# AbbotCameraController.net
KiCad netlist of a schematic drawn in EAGLE
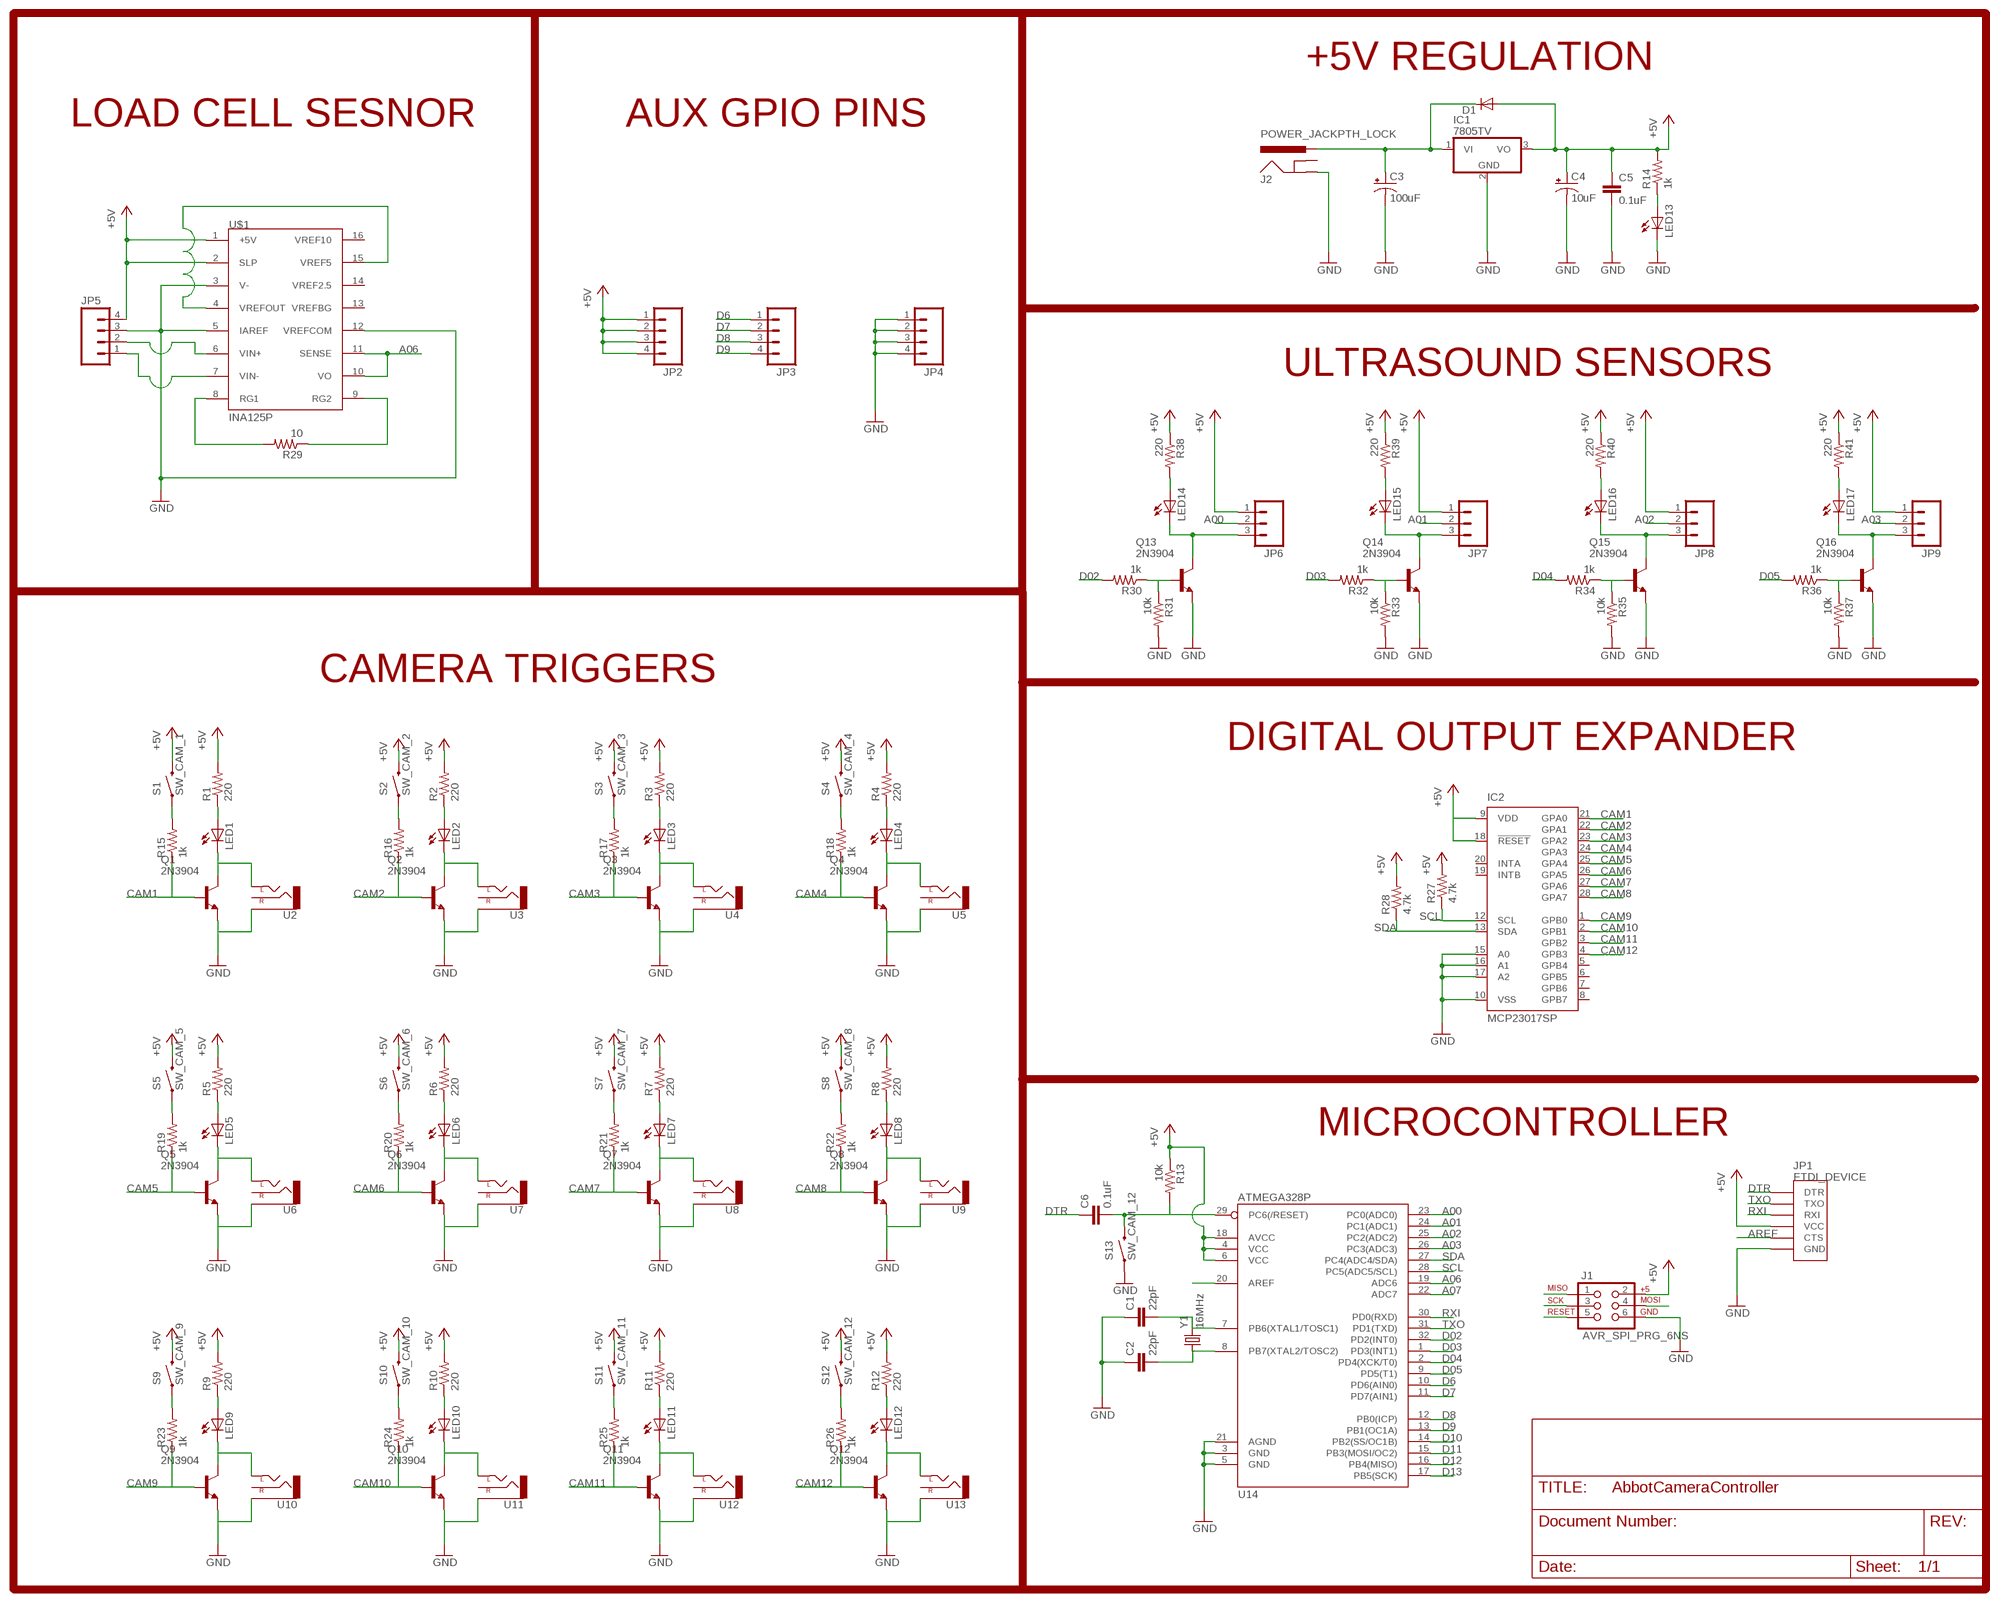
[diagram p0: schematic, sheet 1]

(export (version "E")
  (design (tool "Eeschema 10.0.6"))
  (components
    (comp (ref "C1")
      (value "22pF")
      (footprint "eagle-import:CAP-PTH-SMALL2")
      (libsource (lib "eagle-import") (part "CAPPTH2"))
    )
    (comp (ref "C2")
      (value "22pF")
      (footprint "eagle-import:CAP-PTH-SMALL2")
      (libsource (lib "eagle-import") (part "CAPPTH2"))
    )
    (comp (ref "C3")
      (value "100uF")
      (footprint "eagle-import:E2,5-7")
      (libsource (lib "eagle-import") (part "CPOL-USE2.5-7"))
    )
    (comp (ref "C4")
      (value "10uF")
      (footprint "eagle-import:E2,5-5")
      (libsource (lib "eagle-import") (part "CPOL-USE2.5-5"))
    )
    (comp (ref "C5")
      (value "0.1uF")
      (footprint "eagle-import:C025-025X050")
      (libsource (lib "eagle-import") (part "C-EU025-025X050"))
    )
    (comp (ref "C6")
      (value "0.1uF")
      (footprint "eagle-import:C025-025X050")
      (libsource (lib "eagle-import") (part "C-EU025-025X050"))
    )
    (comp (ref "D1")
      (value "DIODEPTH")
      (footprint "eagle-import:DIODE-1N4001")
      (libsource (lib "eagle-import") (part "DIODEPTH"))
    )
    (comp (ref "IC1")
      (value "7805TV")
      (footprint "eagle-import:TO220V")
      (libsource (lib "eagle-import") (part "78TV05"))
    )
    (comp (ref "IC2")
      (value "MCP23017SP")
      (footprint "eagle-import:DIL28-3")
      (libsource (lib "eagle-import") (part "MCP23017SP"))
    )
    (comp (ref "J1")
      (value "AVR_SPI_PRG_6NS")
      (footprint "eagle-import:2X3-NS")
      (libsource (lib "eagle-import") (part "AVR_SPI_PRG_6NS"))
    )
    (comp (ref "J2")
      (value "POWER_JACKPTH_LOCK")
      (footprint "eagle-import:POWER_JACK_PTH_LOCK")
      (libsource (lib "eagle-import") (part "POWER_JACKPTH_LOCK"))
    )
    (comp (ref "JP1")
      (value "FTDI_DEVICE")
      (footprint "eagle-import:FTDI_DEVICE_SIDE")
      (libsource (lib "eagle-import") (part "FTDI_DEVICE"))
    )
    (comp (ref "JP2")
      (value "M04PTH")
      (footprint "eagle-import:1X04")
      (libsource (lib "eagle-import") (part "M04PTH"))
    )
    (comp (ref "JP3")
      (value "M04PTH")
      (footprint "eagle-import:1X04")
      (libsource (lib "eagle-import") (part "M04PTH"))
    )
    (comp (ref "JP4")
      (value "M04PTH")
      (footprint "eagle-import:1X04")
      (libsource (lib "eagle-import") (part "M04PTH"))
    )
    (comp (ref "JP5")
      (value "M04LONGPADS")
      (footprint "eagle-import:1X04_LONGPADS")
      (libsource (lib "eagle-import") (part "M04LONGPADS"))
    )
    (comp (ref "JP6")
      (value "M03LONGPADS")
      (footprint "eagle-import:1X03_LONGPADS")
      (libsource (lib "eagle-import") (part "M03LONGPADS"))
    )
    (comp (ref "JP7")
      (value "M03LONGPADS")
      (footprint "eagle-import:1X03_LONGPADS")
      (libsource (lib "eagle-import") (part "M03LONGPADS"))
    )
    (comp (ref "JP8")
      (value "M03LONGPADS")
      (footprint "eagle-import:1X03_LONGPADS")
      (libsource (lib "eagle-import") (part "M03LONGPADS"))
    )
    (comp (ref "JP9")
      (value "M03LONGPADS")
      (footprint "eagle-import:1X03_LONGPADS")
      (libsource (lib "eagle-import") (part "M03LONGPADS"))
    )
    (comp (ref "LED1")
      (value "LED5MM")
      (footprint "eagle-import:LED5MM")
      (libsource (lib "eagle-import") (part "LED5MM"))
    )
    (comp (ref "LED2")
      (value "LED5MM")
      (footprint "eagle-import:LED5MM")
      (libsource (lib "eagle-import") (part "LED5MM"))
    )
    (comp (ref "LED3")
      (value "LED5MM")
      (footprint "eagle-import:LED5MM")
      (libsource (lib "eagle-import") (part "LED5MM"))
    )
    (comp (ref "LED4")
      (value "LED5MM")
      (footprint "eagle-import:LED5MM")
      (libsource (lib "eagle-import") (part "LED5MM"))
    )
    (comp (ref "LED5")
      (value "LED5MM")
      (footprint "eagle-import:LED5MM")
      (libsource (lib "eagle-import") (part "LED5MM"))
    )
    (comp (ref "LED6")
      (value "LED5MM")
      (footprint "eagle-import:LED5MM")
      (libsource (lib "eagle-import") (part "LED5MM"))
    )
    (comp (ref "LED7")
      (value "LED5MM")
      (footprint "eagle-import:LED5MM")
      (libsource (lib "eagle-import") (part "LED5MM"))
    )
    (comp (ref "LED8")
      (value "LED5MM")
      (footprint "eagle-import:LED5MM")
      (libsource (lib "eagle-import") (part "LED5MM"))
    )
    (comp (ref "LED9")
      (value "LED5MM")
      (footprint "eagle-import:LED5MM")
      (libsource (lib "eagle-import") (part "LED5MM"))
    )
    (comp (ref "LED10")
      (value "LED5MM")
      (footprint "eagle-import:LED5MM")
      (libsource (lib "eagle-import") (part "LED5MM"))
    )
    (comp (ref "LED11")
      (value "LED5MM")
      (footprint "eagle-import:LED5MM")
      (libsource (lib "eagle-import") (part "LED5MM"))
    )
    (comp (ref "LED12")
      (value "LED5MM")
      (footprint "eagle-import:LED5MM")
      (libsource (lib "eagle-import") (part "LED5MM"))
    )
    (comp (ref "LED13")
      (value "LED5MM")
      (footprint "eagle-import:LED5MM")
      (libsource (lib "eagle-import") (part "LED5MM"))
    )
    (comp (ref "LED14")
      (value "LED5MM")
      (footprint "eagle-import:LED5MM")
      (libsource (lib "eagle-import") (part "LED5MM"))
    )
    (comp (ref "LED15")
      (value "LED5MM")
      (footprint "eagle-import:LED5MM")
      (libsource (lib "eagle-import") (part "LED5MM"))
    )
    (comp (ref "LED16")
      (value "LED5MM")
      (footprint "eagle-import:LED5MM")
      (libsource (lib "eagle-import") (part "LED5MM"))
    )
    (comp (ref "LED17")
      (value "LED5MM")
      (footprint "eagle-import:LED5MM")
      (libsource (lib "eagle-import") (part "LED5MM"))
    )
    (comp (ref "Q1")
      (value "2N3904")
      (footprint "eagle-import:TO92")
      (libsource (lib "eagle-import") (part "2N3904"))
    )
    (comp (ref "Q2")
      (value "2N3904")
      (footprint "eagle-import:TO92")
      (libsource (lib "eagle-import") (part "2N3904"))
    )
    (comp (ref "Q3")
      (value "2N3904")
      (footprint "eagle-import:TO92")
      (libsource (lib "eagle-import") (part "2N3904"))
    )
    (comp (ref "Q4")
      (value "2N3904")
      (footprint "eagle-import:TO92")
      (libsource (lib "eagle-import") (part "2N3904"))
    )
    (comp (ref "Q5")
      (value "2N3904")
      (footprint "eagle-import:TO92")
      (libsource (lib "eagle-import") (part "2N3904"))
    )
    (comp (ref "Q6")
      (value "2N3904")
      (footprint "eagle-import:TO92")
      (libsource (lib "eagle-import") (part "2N3904"))
    )
    (comp (ref "Q7")
      (value "2N3904")
      (footprint "eagle-import:TO92")
      (libsource (lib "eagle-import") (part "2N3904"))
    )
    (comp (ref "Q8")
      (value "2N3904")
      (footprint "eagle-import:TO92")
      (libsource (lib "eagle-import") (part "2N3904"))
    )
    (comp (ref "Q9")
      (value "2N3904")
      (footprint "eagle-import:TO92")
      (libsource (lib "eagle-import") (part "2N3904"))
    )
    (comp (ref "Q10")
      (value "2N3904")
      (footprint "eagle-import:TO92")
      (libsource (lib "eagle-import") (part "2N3904"))
    )
    (comp (ref "Q11")
      (value "2N3904")
      (footprint "eagle-import:TO92")
      (libsource (lib "eagle-import") (part "2N3904"))
    )
    (comp (ref "Q12")
      (value "2N3904")
      (footprint "eagle-import:TO92")
      (libsource (lib "eagle-import") (part "2N3904"))
    )
    (comp (ref "Q13")
      (value "2N3904")
      (footprint "eagle-import:TO92")
      (libsource (lib "eagle-import") (part "2N3904"))
    )
    (comp (ref "Q14")
      (value "2N3904")
      (footprint "eagle-import:TO92")
      (libsource (lib "eagle-import") (part "2N3904"))
    )
    (comp (ref "Q15")
      (value "2N3904")
      (footprint "eagle-import:TO92")
      (libsource (lib "eagle-import") (part "2N3904"))
    )
    (comp (ref "Q16")
      (value "2N3904")
      (footprint "eagle-import:TO92")
      (libsource (lib "eagle-import") (part "2N3904"))
    )
    (comp (ref "R1")
      (value "220")
      (footprint "eagle-import:0207_10")
      (libsource (lib "eagle-import") (part "R-US_0207/10"))
    )
    (comp (ref "R2")
      (value "220")
      (footprint "eagle-import:0207_10")
      (libsource (lib "eagle-import") (part "R-US_0207/10"))
    )
    (comp (ref "R3")
      (value "220")
      (footprint "eagle-import:0207_10")
      (libsource (lib "eagle-import") (part "R-US_0207/10"))
    )
    (comp (ref "R4")
      (value "220")
      (footprint "eagle-import:0207_10")
      (libsource (lib "eagle-import") (part "R-US_0207/10"))
    )
    (comp (ref "R5")
      (value "220")
      (footprint "eagle-import:0207_10")
      (libsource (lib "eagle-import") (part "R-US_0207/10"))
    )
    (comp (ref "R6")
      (value "220")
      (footprint "eagle-import:0207_10")
      (libsource (lib "eagle-import") (part "R-US_0207/10"))
    )
    (comp (ref "R7")
      (value "220")
      (footprint "eagle-import:0207_10")
      (libsource (lib "eagle-import") (part "R-US_0207/10"))
    )
    (comp (ref "R8")
      (value "220")
      (footprint "eagle-import:0207_10")
      (libsource (lib "eagle-import") (part "R-US_0207/10"))
    )
    (comp (ref "R9")
      (value "220")
      (footprint "eagle-import:0207_10")
      (libsource (lib "eagle-import") (part "R-US_0207/10"))
    )
    (comp (ref "R10")
      (value "220")
      (footprint "eagle-import:0207_10")
      (libsource (lib "eagle-import") (part "R-US_0207/10"))
    )
    (comp (ref "R11")
      (value "220")
      (footprint "eagle-import:0207_10")
      (libsource (lib "eagle-import") (part "R-US_0207/10"))
    )
    (comp (ref "R12")
      (value "220")
      (footprint "eagle-import:0207_10")
      (libsource (lib "eagle-import") (part "R-US_0207/10"))
    )
    (comp (ref "R13")
      (value "10k")
      (footprint "eagle-import:0207_10")
      (libsource (lib "eagle-import") (part "R-US_0207/10"))
    )
    (comp (ref "R14")
      (value "1k")
      (footprint "eagle-import:0207_10")
      (libsource (lib "eagle-import") (part "R-US_0207/10"))
    )
    (comp (ref "R15")
      (value "1k")
      (footprint "eagle-import:0207_10")
      (libsource (lib "eagle-import") (part "R-US_0207/10"))
    )
    (comp (ref "R16")
      (value "1k")
      (footprint "eagle-import:0207_10")
      (libsource (lib "eagle-import") (part "R-US_0207/10"))
    )
    (comp (ref "R17")
      (value "1k")
      (footprint "eagle-import:0207_10")
      (libsource (lib "eagle-import") (part "R-US_0207/10"))
    )
    (comp (ref "R18")
      (value "1k")
      (footprint "eagle-import:0207_10")
      (libsource (lib "eagle-import") (part "R-US_0207/10"))
    )
    (comp (ref "R19")
      (value "1k")
      (footprint "eagle-import:0207_10")
      (libsource (lib "eagle-import") (part "R-US_0207/10"))
    )
    (comp (ref "R20")
      (value "1k")
      (footprint "eagle-import:0207_10")
      (libsource (lib "eagle-import") (part "R-US_0207/10"))
    )
    (comp (ref "R21")
      (value "1k")
      (footprint "eagle-import:0207_10")
      (libsource (lib "eagle-import") (part "R-US_0207/10"))
    )
    (comp (ref "R22")
      (value "1k")
      (footprint "eagle-import:0207_10")
      (libsource (lib "eagle-import") (part "R-US_0207/10"))
    )
    (comp (ref "R23")
      (value "1k")
      (footprint "eagle-import:0207_10")
      (libsource (lib "eagle-import") (part "R-US_0207/10"))
    )
    (comp (ref "R24")
      (value "1k")
      (footprint "eagle-import:0207_10")
      (libsource (lib "eagle-import") (part "R-US_0207/10"))
    )
    (comp (ref "R25")
      (value "1k")
      (footprint "eagle-import:0207_10")
      (libsource (lib "eagle-import") (part "R-US_0207/10"))
    )
    (comp (ref "R26")
      (value "1k")
      (footprint "eagle-import:0207_10")
      (libsource (lib "eagle-import") (part "R-US_0207/10"))
    )
    (comp (ref "R27")
      (value "4.7k")
      (footprint "eagle-import:0207_10")
      (libsource (lib "eagle-import") (part "R-US_0207/10"))
    )
    (comp (ref "R28")
      (value "4.7k")
      (footprint "eagle-import:0207_10")
      (libsource (lib "eagle-import") (part "R-US_0207/10"))
    )
    (comp (ref "R29")
      (value "10")
      (footprint "eagle-import:0207_10")
      (libsource (lib "eagle-import") (part "R-US_0207/10"))
    )
    (comp (ref "R30")
      (value "1k")
      (footprint "eagle-import:0207_10")
      (libsource (lib "eagle-import") (part "R-US_0207/10"))
    )
    (comp (ref "R31")
      (value "10k")
      (footprint "eagle-import:0207_10")
      (libsource (lib "eagle-import") (part "R-US_0207/10"))
    )
    (comp (ref "R32")
      (value "1k")
      (footprint "eagle-import:0207_10")
      (libsource (lib "eagle-import") (part "R-US_0207/10"))
    )
    (comp (ref "R33")
      (value "10k")
      (footprint "eagle-import:0207_10")
      (libsource (lib "eagle-import") (part "R-US_0207/10"))
    )
    (comp (ref "R34")
      (value "1k")
      (footprint "eagle-import:0207_10")
      (libsource (lib "eagle-import") (part "R-US_0207/10"))
    )
    (comp (ref "R35")
      (value "10k")
      (footprint "eagle-import:0207_10")
      (libsource (lib "eagle-import") (part "R-US_0207/10"))
    )
    (comp (ref "R36")
      (value "1k")
      (footprint "eagle-import:0207_10")
      (libsource (lib "eagle-import") (part "R-US_0207/10"))
    )
    (comp (ref "R37")
      (value "10k")
      (footprint "eagle-import:0207_10")
      (libsource (lib "eagle-import") (part "R-US_0207/10"))
    )
    (comp (ref "R38")
      (value "220")
      (footprint "eagle-import:0207_10")
      (libsource (lib "eagle-import") (part "R-US_0207/10"))
    )
    (comp (ref "R39")
      (value "220")
      (footprint "eagle-import:0207_10")
      (libsource (lib "eagle-import") (part "R-US_0207/10"))
    )
    (comp (ref "R40")
      (value "220")
      (footprint "eagle-import:0207_10")
      (libsource (lib "eagle-import") (part "R-US_0207/10"))
    )
    (comp (ref "R41")
      (value "220")
      (footprint "eagle-import:0207_10")
      (libsource (lib "eagle-import") (part "R-US_0207/10"))
    )
    (comp (ref "S1")
      (value "SW_CAM_1")
      (footprint "eagle-import:TACTILE-PTH")
      (libsource (lib "eagle-import") (part "SWITCH-MOMENTARY-2PTH"))
    )
    (comp (ref "S2")
      (value "SW_CAM_2")
      (footprint "eagle-import:TACTILE-PTH")
      (libsource (lib "eagle-import") (part "SWITCH-MOMENTARY-2PTH"))
    )
    (comp (ref "S3")
      (value "SW_CAM_3")
      (footprint "eagle-import:TACTILE-PTH")
      (libsource (lib "eagle-import") (part "SWITCH-MOMENTARY-2PTH"))
    )
    (comp (ref "S4")
      (value "SW_CAM_4")
      (footprint "eagle-import:TACTILE-PTH")
      (libsource (lib "eagle-import") (part "SWITCH-MOMENTARY-2PTH"))
    )
    (comp (ref "S5")
      (value "SW_CAM_5")
      (footprint "eagle-import:TACTILE-PTH")
      (libsource (lib "eagle-import") (part "SWITCH-MOMENTARY-2PTH"))
    )
    (comp (ref "S6")
      (value "SW_CAM_6")
      (footprint "eagle-import:TACTILE-PTH")
      (libsource (lib "eagle-import") (part "SWITCH-MOMENTARY-2PTH"))
    )
    (comp (ref "S7")
      (value "SW_CAM_7")
      (footprint "eagle-import:TACTILE-PTH")
      (libsource (lib "eagle-import") (part "SWITCH-MOMENTARY-2PTH"))
    )
    (comp (ref "S8")
      (value "SW_CAM_8")
      (footprint "eagle-import:TACTILE-PTH")
      (libsource (lib "eagle-import") (part "SWITCH-MOMENTARY-2PTH"))
    )
    (comp (ref "S9")
      (value "SW_CAM_9")
      (footprint "eagle-import:TACTILE-PTH")
      (libsource (lib "eagle-import") (part "SWITCH-MOMENTARY-2PTH"))
    )
    (comp (ref "S10")
      (value "SW_CAM_10")
      (footprint "eagle-import:TACTILE-PTH")
      (libsource (lib "eagle-import") (part "SWITCH-MOMENTARY-2PTH"))
    )
    (comp (ref "S11")
      (value "SW_CAM_11")
      (footprint "eagle-import:TACTILE-PTH")
      (libsource (lib "eagle-import") (part "SWITCH-MOMENTARY-2PTH"))
    )
    (comp (ref "S12")
      (value "SW_CAM_12")
      (footprint "eagle-import:TACTILE-PTH")
      (libsource (lib "eagle-import") (part "SWITCH-MOMENTARY-2PTH"))
    )
    (comp (ref "S13")
      (value "SW_CAM_12")
      (footprint "eagle-import:TACTILE-PTH")
      (libsource (lib "eagle-import") (part "SWITCH-MOMENTARY-2PTH"))
    )
    (comp (ref "U$1")
      (value "INA125P")
      (footprint "eagle-import:16-DIP")
      (libsource (lib "eagle-import") (part "INA125P"))
    )
    (comp (ref "U2")
      (value "AUDIO-JACKSPECIAL_POGO_PINS")
      (footprint "eagle-import:STEREOJACK2.5MM_SPECIA_POGOPINS")
      (libsource (lib "eagle-import") (part "AUDIO-JACKSPECIAL_POGO_PINS"))
    )
    (comp (ref "U3")
      (value "AUDIO-JACKSPECIAL_POGO_PINS")
      (footprint "eagle-import:STEREOJACK2.5MM_SPECIA_POGOPINS")
      (libsource (lib "eagle-import") (part "AUDIO-JACKSPECIAL_POGO_PINS"))
    )
    (comp (ref "U4")
      (value "AUDIO-JACKSPECIAL_POGO_PINS")
      (footprint "eagle-import:STEREOJACK2.5MM_SPECIA_POGOPINS")
      (libsource (lib "eagle-import") (part "AUDIO-JACKSPECIAL_POGO_PINS"))
    )
    (comp (ref "U5")
      (value "AUDIO-JACKSPECIAL_POGO_PINS")
      (footprint "eagle-import:STEREOJACK2.5MM_SPECIA_POGOPINS")
      (libsource (lib "eagle-import") (part "AUDIO-JACKSPECIAL_POGO_PINS"))
    )
    (comp (ref "U6")
      (value "AUDIO-JACKSPECIAL_POGO_PINS")
      (footprint "eagle-import:STEREOJACK2.5MM_SPECIA_POGOPINS")
      (libsource (lib "eagle-import") (part "AUDIO-JACKSPECIAL_POGO_PINS"))
    )
    (comp (ref "U7")
      (value "AUDIO-JACKSPECIAL_POGO_PINS")
      (footprint "eagle-import:STEREOJACK2.5MM_SPECIA_POGOPINS")
      (libsource (lib "eagle-import") (part "AUDIO-JACKSPECIAL_POGO_PINS"))
    )
    (comp (ref "U8")
      (value "AUDIO-JACKSPECIAL_POGO_PINS")
      (footprint "eagle-import:STEREOJACK2.5MM_SPECIA_POGOPINS")
      (libsource (lib "eagle-import") (part "AUDIO-JACKSPECIAL_POGO_PINS"))
    )
    (comp (ref "U9")
      (value "AUDIO-JACKSPECIAL_POGO_PINS")
      (footprint "eagle-import:STEREOJACK2.5MM_SPECIA_POGOPINS")
      (libsource (lib "eagle-import") (part "AUDIO-JACKSPECIAL_POGO_PINS"))
    )
    (comp (ref "U10")
      (value "AUDIO-JACKSPECIAL_POGO_PINS")
      (footprint "eagle-import:STEREOJACK2.5MM_SPECIA_POGOPINS")
      (libsource (lib "eagle-import") (part "AUDIO-JACKSPECIAL_POGO_PINS"))
    )
    (comp (ref "U11")
      (value "AUDIO-JACKSPECIAL_POGO_PINS")
      (footprint "eagle-import:STEREOJACK2.5MM_SPECIA_POGOPINS")
      (libsource (lib "eagle-import") (part "AUDIO-JACKSPECIAL_POGO_PINS"))
    )
    (comp (ref "U12")
      (value "AUDIO-JACKSPECIAL_POGO_PINS")
      (footprint "eagle-import:STEREOJACK2.5MM_SPECIA_POGOPINS")
      (libsource (lib "eagle-import") (part "AUDIO-JACKSPECIAL_POGO_PINS"))
    )
    (comp (ref "U13")
      (value "AUDIO-JACKSPECIAL_POGO_PINS")
      (footprint "eagle-import:STEREOJACK2.5MM_SPECIA_POGOPINS")
      (libsource (lib "eagle-import") (part "AUDIO-JACKSPECIAL_POGO_PINS"))
    )
    (comp (ref "U14")
      (value "ATMEGA328P")
      (footprint "eagle-import:TQFP32-08")
      (libsource (lib "eagle-import") (part "ATMEGA328_SMT"))
    )
    (comp (ref "Y1")
      (value "16MHz")
      (footprint "eagle-import:HC49US")
      (libsource (lib "eagle-import") (part "CRYSTALHC49US"))
    )
  )
  (nets
    (net (code "1") (name "+5V") (class "Default")
      (node (ref "C4") (pin "+") (pinfunction "+_+") (pintype "passive"))
      (node (ref "C5") (pin "1") (pinfunction "1_1") (pintype "passive"))
      (node (ref "D1") (pin "A") (pinfunction "A_A") (pintype "passive"))
      (node (ref "IC1") (pin "3") (pinfunction "VO_3") (pintype "passive"))
      (node (ref "IC2") (pin "18") (pinfunction "~{RESET}_18") (pintype "input"))
      (node (ref "IC2") (pin "9") (pinfunction "VDD_9") (pintype "power_in"))
      (node (ref "J1") (pin "2") (pinfunction "2_2") (pintype "passive"))
      (node (ref "JP1") (pin "P$4") (pinfunction "VCC_P$4") (pintype "bidirectional"))
      (node (ref "JP2") (pin "1") (pinfunction "1_1") (pintype "passive"))
      (node (ref "JP2") (pin "2") (pinfunction "2_2") (pintype "passive"))
      (node (ref "JP2") (pin "3") (pinfunction "3_3") (pintype "passive"))
      (node (ref "JP2") (pin "4") (pinfunction "4_4") (pintype "passive"))
      (node (ref "JP5") (pin "4") (pinfunction "4_4") (pintype "passive"))
      (node (ref "JP6") (pin "1") (pinfunction "1_1") (pintype "passive"))
      (node (ref "JP7") (pin "1") (pinfunction "1_1") (pintype "passive"))
      (node (ref "JP8") (pin "1") (pinfunction "1_1") (pintype "passive"))
      (node (ref "JP9") (pin "1") (pinfunction "1_1") (pintype "passive"))
      (node (ref "R1") (pin "2") (pinfunction "2_2") (pintype "passive"))
      (node (ref "R10") (pin "2") (pinfunction "2_2") (pintype "passive"))
      (node (ref "R11") (pin "2") (pinfunction "2_2") (pintype "passive"))
      (node (ref "R12") (pin "2") (pinfunction "2_2") (pintype "passive"))
      (node (ref "R13") (pin "1") (pinfunction "1_1") (pintype "passive"))
      (node (ref "R14") (pin "2") (pinfunction "2_2") (pintype "passive"))
      (node (ref "R2") (pin "2") (pinfunction "2_2") (pintype "passive"))
      (node (ref "R27") (pin "2") (pinfunction "2_2") (pintype "passive"))
      (node (ref "R28") (pin "2") (pinfunction "2_2") (pintype "passive"))
      (node (ref "R3") (pin "2") (pinfunction "2_2") (pintype "passive"))
      (node (ref "R38") (pin "1") (pinfunction "1_1") (pintype "passive"))
      (node (ref "R39") (pin "1") (pinfunction "1_1") (pintype "passive"))
      (node (ref "R4") (pin "2") (pinfunction "2_2") (pintype "passive"))
      (node (ref "R40") (pin "1") (pinfunction "1_1") (pintype "passive"))
      (node (ref "R41") (pin "1") (pinfunction "1_1") (pintype "passive"))
      (node (ref "R5") (pin "2") (pinfunction "2_2") (pintype "passive"))
      (node (ref "R6") (pin "2") (pinfunction "2_2") (pintype "passive"))
      (node (ref "R7") (pin "2") (pinfunction "2_2") (pintype "passive"))
      (node (ref "R8") (pin "2") (pinfunction "2_2") (pintype "passive"))
      (node (ref "R9") (pin "2") (pinfunction "2_2") (pintype "passive"))
      (node (ref "S1") (pin "3") (pinfunction "2_3") (pintype "passive"))
      (node (ref "S10") (pin "3") (pinfunction "2_3") (pintype "passive"))
      (node (ref "S11") (pin "3") (pinfunction "2_3") (pintype "passive"))
      (node (ref "S12") (pin "3") (pinfunction "2_3") (pintype "passive"))
      (node (ref "S2") (pin "3") (pinfunction "2_3") (pintype "passive"))
      (node (ref "S3") (pin "3") (pinfunction "2_3") (pintype "passive"))
      (node (ref "S4") (pin "3") (pinfunction "2_3") (pintype "passive"))
      (node (ref "S5") (pin "3") (pinfunction "2_3") (pintype "passive"))
      (node (ref "S6") (pin "3") (pinfunction "2_3") (pintype "passive"))
      (node (ref "S7") (pin "3") (pinfunction "2_3") (pintype "passive"))
      (node (ref "S8") (pin "3") (pinfunction "2_3") (pintype "passive"))
      (node (ref "S9") (pin "3") (pinfunction "2_3") (pintype "passive"))
      (node (ref "U$1") (pin "1") (pinfunction "+5V_1") (pintype "bidirectional"))
      (node (ref "U$1") (pin "2") (pinfunction "SLP_2") (pintype "bidirectional"))
      (node (ref "U14") (pin "18") (pinfunction "AVCC_18") (pintype "bidirectional"))
      (node (ref "U14") (pin "4") (pinfunction "VCC_4") (pintype "bidirectional"))
      (node (ref "U14") (pin "6") (pinfunction "VCC_6") (pintype "bidirectional"))
    )
    (net (code "2") (name "/A00") (class "Default")
      (node (ref "JP6") (pin "2") (pinfunction "2_2") (pintype "passive"))
      (node (ref "U14") (pin "23") (pinfunction "PC0(ADC0)_23") (pintype "bidirectional"))
    )
    (net (code "3") (name "/A01") (class "Default")
      (node (ref "JP7") (pin "2") (pinfunction "2_2") (pintype "passive"))
      (node (ref "U14") (pin "24") (pinfunction "PC1(ADC1)_24") (pintype "bidirectional"))
    )
    (net (code "4") (name "/A02") (class "Default")
      (node (ref "JP8") (pin "2") (pinfunction "2_2") (pintype "passive"))
      (node (ref "U14") (pin "25") (pinfunction "PC2(ADC2)_25") (pintype "bidirectional"))
    )
    (net (code "5") (name "/A03") (class "Default")
      (node (ref "JP9") (pin "2") (pinfunction "2_2") (pintype "passive"))
      (node (ref "U14") (pin "26") (pinfunction "PC3(ADC3)_26") (pintype "bidirectional"))
    )
    (net (code "6") (name "/A06") (class "Default")
      (node (ref "U$1") (pin "10") (pinfunction "VO_10") (pintype "bidirectional"))
      (node (ref "U$1") (pin "11") (pinfunction "SENSE_11") (pintype "bidirectional"))
      (node (ref "U14") (pin "19") (pinfunction "ADC6_19") (pintype "bidirectional"))
    )
    (net (code "7") (name "/A07") (class "Default")
      (node (ref "U14") (pin "22") (pinfunction "ADC7_22") (pintype "bidirectional"))
    )
    (net (code "8") (name "/AREF") (class "Default")
      (node (ref "JP1") (pin "P$5") (pinfunction "CTS_P$5") (pintype "bidirectional"))
      (node (ref "U14") (pin "20") (pinfunction "AREF_20") (pintype "bidirectional"))
    )
    (net (code "9") (name "/CAM1") (class "Default")
      (node (ref "IC2") (pin "21") (pinfunction "GPA0_21") (pintype "bidirectional"))
      (node (ref "Q1") (pin "2") (pinfunction "B_2") (pintype "passive"))
      (node (ref "R15") (pin "1") (pinfunction "1_1") (pintype "passive"))
    )
    (net (code "10") (name "/CAM2") (class "Default")
      (node (ref "IC2") (pin "22") (pinfunction "GPA1_22") (pintype "bidirectional"))
      (node (ref "Q2") (pin "2") (pinfunction "B_2") (pintype "passive"))
      (node (ref "R16") (pin "1") (pinfunction "1_1") (pintype "passive"))
    )
    (net (code "11") (name "/CAM3") (class "Default")
      (node (ref "IC2") (pin "23") (pinfunction "GPA2_23") (pintype "bidirectional"))
      (node (ref "Q3") (pin "2") (pinfunction "B_2") (pintype "passive"))
      (node (ref "R17") (pin "1") (pinfunction "1_1") (pintype "passive"))
    )
    (net (code "12") (name "/CAM4") (class "Default")
      (node (ref "IC2") (pin "24") (pinfunction "GPA3_24") (pintype "bidirectional"))
      (node (ref "Q4") (pin "2") (pinfunction "B_2") (pintype "passive"))
      (node (ref "R18") (pin "1") (pinfunction "1_1") (pintype "passive"))
    )
    (net (code "13") (name "/CAM5") (class "Default")
      (node (ref "IC2") (pin "25") (pinfunction "GPA4_25") (pintype "bidirectional"))
      (node (ref "Q5") (pin "2") (pinfunction "B_2") (pintype "passive"))
      (node (ref "R19") (pin "1") (pinfunction "1_1") (pintype "passive"))
    )
    (net (code "14") (name "/CAM6") (class "Default")
      (node (ref "IC2") (pin "26") (pinfunction "GPA5_26") (pintype "bidirectional"))
      (node (ref "Q6") (pin "2") (pinfunction "B_2") (pintype "passive"))
      (node (ref "R20") (pin "1") (pinfunction "1_1") (pintype "passive"))
    )
    (net (code "15") (name "/CAM7") (class "Default")
      (node (ref "IC2") (pin "27") (pinfunction "GPA6_27") (pintype "bidirectional"))
      (node (ref "Q7") (pin "2") (pinfunction "B_2") (pintype "passive"))
      (node (ref "R21") (pin "1") (pinfunction "1_1") (pintype "passive"))
    )
    (net (code "16") (name "/CAM8") (class "Default")
      (node (ref "IC2") (pin "28") (pinfunction "GPA7_28") (pintype "bidirectional"))
      (node (ref "Q8") (pin "2") (pinfunction "B_2") (pintype "passive"))
      (node (ref "R22") (pin "1") (pinfunction "1_1") (pintype "passive"))
    )
    (net (code "17") (name "/CAM9") (class "Default")
      (node (ref "IC2") (pin "1") (pinfunction "GPB0_1") (pintype "bidirectional"))
      (node (ref "Q9") (pin "2") (pinfunction "B_2") (pintype "passive"))
      (node (ref "R23") (pin "1") (pinfunction "1_1") (pintype "passive"))
    )
    (net (code "18") (name "/CAM10") (class "Default")
      (node (ref "IC2") (pin "2") (pinfunction "GPB1_2") (pintype "bidirectional"))
      (node (ref "Q10") (pin "2") (pinfunction "B_2") (pintype "passive"))
      (node (ref "R24") (pin "1") (pinfunction "1_1") (pintype "passive"))
    )
    (net (code "19") (name "/CAM11") (class "Default")
      (node (ref "IC2") (pin "3") (pinfunction "GPB2_3") (pintype "bidirectional"))
      (node (ref "Q11") (pin "2") (pinfunction "B_2") (pintype "passive"))
      (node (ref "R25") (pin "1") (pinfunction "1_1") (pintype "passive"))
    )
    (net (code "20") (name "/CAM12") (class "Default")
      (node (ref "IC2") (pin "4") (pinfunction "GPB3_4") (pintype "bidirectional"))
      (node (ref "Q12") (pin "2") (pinfunction "B_2") (pintype "passive"))
      (node (ref "R26") (pin "1") (pinfunction "1_1") (pintype "passive"))
    )
    (net (code "21") (name "/D02") (class "Default")
      (node (ref "R30") (pin "2") (pinfunction "2_2") (pintype "passive"))
      (node (ref "U14") (pin "32") (pinfunction "PD2(INT0)_32") (pintype "bidirectional"))
    )
    (net (code "22") (name "/D03") (class "Default")
      (node (ref "R32") (pin "2") (pinfunction "2_2") (pintype "passive"))
      (node (ref "U14") (pin "1") (pinfunction "PD3(INT1)_1") (pintype "bidirectional"))
    )
    (net (code "23") (name "/D04") (class "Default")
      (node (ref "R34") (pin "2") (pinfunction "2_2") (pintype "passive"))
      (node (ref "U14") (pin "2") (pinfunction "PD4(XCK/T0)_2") (pintype "bidirectional"))
    )
    (net (code "24") (name "/D05") (class "Default")
      (node (ref "R36") (pin "2") (pinfunction "2_2") (pintype "passive"))
      (node (ref "U14") (pin "9") (pinfunction "PD5(T1)_9") (pintype "bidirectional"))
    )
    (net (code "25") (name "/D6") (class "Default")
      (node (ref "JP3") (pin "1") (pinfunction "1_1") (pintype "passive"))
      (node (ref "U14") (pin "10") (pinfunction "PD6(AIN0)_10") (pintype "bidirectional"))
    )
    (net (code "26") (name "/D7") (class "Default")
      (node (ref "JP3") (pin "2") (pinfunction "2_2") (pintype "passive"))
      (node (ref "U14") (pin "11") (pinfunction "PD7(AIN1)_11") (pintype "bidirectional"))
    )
    (net (code "27") (name "/D8") (class "Default")
      (node (ref "JP3") (pin "3") (pinfunction "3_3") (pintype "passive"))
      (node (ref "U14") (pin "12") (pinfunction "PB0(ICP)_12") (pintype "bidirectional"))
    )
    (net (code "28") (name "/D9") (class "Default")
      (node (ref "JP3") (pin "4") (pinfunction "4_4") (pintype "passive"))
      (node (ref "U14") (pin "13") (pinfunction "PB1(OC1A)_13") (pintype "bidirectional"))
    )
    (net (code "29") (name "/D10") (class "Default")
      (node (ref "U14") (pin "14") (pinfunction "PB2(SS/OC1B)_14") (pintype "bidirectional"))
    )
    (net (code "30") (name "/D11") (class "Default")
      (node (ref "J1") (pin "4") (pinfunction "4_4") (pintype "passive"))
      (node (ref "U14") (pin "15") (pinfunction "PB3(MOSI/OC2)_15") (pintype "bidirectional"))
    )
    (net (code "31") (name "/D12") (class "Default")
      (node (ref "J1") (pin "1") (pinfunction "1_1") (pintype "passive"))
      (node (ref "U14") (pin "16") (pinfunction "PB4(MISO)_16") (pintype "bidirectional"))
    )
    (net (code "32") (name "/D13") (class "Default")
      (node (ref "J1") (pin "3") (pinfunction "3_3") (pintype "passive"))
      (node (ref "U14") (pin "17") (pinfunction "PB5(SCK)_17") (pintype "bidirectional"))
    )
    (net (code "33") (name "/DTR") (class "Default")
      (node (ref "C6") (pin "1") (pinfunction "1_1") (pintype "passive"))
      (node (ref "JP1") (pin "P$1") (pinfunction "DTR_P$1") (pintype "bidirectional"))
    )
    (net (code "34") (name "/RST") (class "Default")
      (node (ref "C6") (pin "2") (pinfunction "2_2") (pintype "passive"))
      (node (ref "J1") (pin "5") (pinfunction "5_5") (pintype "passive"))
      (node (ref "R13") (pin "2") (pinfunction "2_2") (pintype "passive"))
      (node (ref "S13") (pin "3") (pinfunction "2_3") (pintype "passive"))
      (node (ref "U14") (pin "29") (pinfunction "PC6(/RESET)_29") (pintype "bidirectional"))
    )
    (net (code "35") (name "/RXI") (class "Default")
      (node (ref "JP1") (pin "P$3") (pinfunction "RXI_P$3") (pintype "bidirectional"))
      (node (ref "U14") (pin "30") (pinfunction "PD0(RXD)_30") (pintype "bidirectional"))
    )
    (net (code "36") (name "/SCL") (class "Default")
      (node (ref "IC2") (pin "12") (pinfunction "SCL_12") (pintype "input"))
      (node (ref "R27") (pin "1") (pinfunction "1_1") (pintype "passive"))
      (node (ref "U14") (pin "28") (pinfunction "PC5(ADC5/SCL)_28") (pintype "bidirectional"))
    )
    (net (code "37") (name "/SDA") (class "Default")
      (node (ref "IC2") (pin "13") (pinfunction "SDA_13") (pintype "bidirectional"))
      (node (ref "R28") (pin "1") (pinfunction "1_1") (pintype "passive"))
      (node (ref "U14") (pin "27") (pinfunction "PC4(ADC4/SDA)_27") (pintype "bidirectional"))
    )
    (net (code "38") (name "/TXO") (class "Default")
      (node (ref "JP1") (pin "P$2") (pinfunction "TXO_P$2") (pintype "bidirectional"))
      (node (ref "U14") (pin "31") (pinfunction "PD1(TXD)_31") (pintype "bidirectional"))
    )
    (net (code "39") (name "GND") (class "Default")
      (node (ref "C1") (pin "1") (pinfunction "1_1") (pintype "passive"))
      (node (ref "C2") (pin "1") (pinfunction "1_1") (pintype "passive"))
      (node (ref "C3") (pin "-") (pinfunction "-_-") (pintype "passive"))
      (node (ref "C4") (pin "-") (pinfunction "-_-") (pintype "passive"))
      (node (ref "C5") (pin "2") (pinfunction "2_2") (pintype "passive"))
      (node (ref "IC1") (pin "2") (pinfunction "GND_2") (pintype "passive"))
      (node (ref "IC2") (pin "10") (pinfunction "VSS_10") (pintype "power_in"))
      (node (ref "IC2") (pin "15") (pinfunction "A0_15") (pintype "input"))
      (node (ref "IC2") (pin "16") (pinfunction "A1_16") (pintype "input"))
      (node (ref "IC2") (pin "17") (pinfunction "A2_17") (pintype "input"))
      (node (ref "J1") (pin "6") (pinfunction "6_6") (pintype "passive"))
      (node (ref "J2") (pin "GND") (pinfunction "GND_GND") (pintype "bidirectional"))
      (node (ref "JP1") (pin "P$6") (pinfunction "GND_P$6") (pintype "bidirectional"))
      (node (ref "JP4") (pin "1") (pinfunction "1_1") (pintype "passive"))
      (node (ref "JP4") (pin "2") (pinfunction "2_2") (pintype "passive"))
      (node (ref "JP4") (pin "3") (pinfunction "3_3") (pintype "passive"))
      (node (ref "JP4") (pin "4") (pinfunction "4_4") (pintype "passive"))
      (node (ref "JP5") (pin "3") (pinfunction "3_3") (pintype "passive"))
      (node (ref "LED13") (pin "K") (pinfunction "C_K") (pintype "passive"))
      (node (ref "Q1") (pin "3") (pinfunction "E_3") (pintype "passive"))
      (node (ref "Q10") (pin "3") (pinfunction "E_3") (pintype "passive"))
      (node (ref "Q11") (pin "3") (pinfunction "E_3") (pintype "passive"))
      (node (ref "Q12") (pin "3") (pinfunction "E_3") (pintype "passive"))
      (node (ref "Q13") (pin "3") (pinfunction "E_3") (pintype "passive"))
      (node (ref "Q14") (pin "3") (pinfunction "E_3") (pintype "passive"))
      (node (ref "Q15") (pin "3") (pinfunction "E_3") (pintype "passive"))
      (node (ref "Q16") (pin "3") (pinfunction "E_3") (pintype "passive"))
      (node (ref "Q2") (pin "3") (pinfunction "E_3") (pintype "passive"))
      (node (ref "Q3") (pin "3") (pinfunction "E_3") (pintype "passive"))
      (node (ref "Q4") (pin "3") (pinfunction "E_3") (pintype "passive"))
      (node (ref "Q5") (pin "3") (pinfunction "E_3") (pintype "passive"))
      (node (ref "Q6") (pin "3") (pinfunction "E_3") (pintype "passive"))
      (node (ref "Q7") (pin "3") (pinfunction "E_3") (pintype "passive"))
      (node (ref "Q8") (pin "3") (pinfunction "E_3") (pintype "passive"))
      (node (ref "Q9") (pin "3") (pinfunction "E_3") (pintype "passive"))
      (node (ref "R31") (pin "2") (pinfunction "2_2") (pintype "passive"))
      (node (ref "R33") (pin "2") (pinfunction "2_2") (pintype "passive"))
      (node (ref "R35") (pin "2") (pinfunction "2_2") (pintype "passive"))
      (node (ref "R37") (pin "2") (pinfunction "2_2") (pintype "passive"))
      (node (ref "S13") (pin "1") (pinfunction "1_1") (pintype "passive"))
      (node (ref "U$1") (pin "12") (pinfunction "VREFCOM_12") (pintype "bidirectional"))
      (node (ref "U$1") (pin "3") (pinfunction "V-_3") (pintype "bidirectional"))
      (node (ref "U$1") (pin "5") (pinfunction "IAREF_5") (pintype "bidirectional"))
      (node (ref "U10") (pin "RING1") (pinfunction "SLEEVE_RING1") (pintype "bidirectional"))
      (node (ref "U11") (pin "RING1") (pinfunction "SLEEVE_RING1") (pintype "bidirectional"))
      (node (ref "U12") (pin "RING1") (pinfunction "SLEEVE_RING1") (pintype "bidirectional"))
      (node (ref "U13") (pin "RING1") (pinfunction "SLEEVE_RING1") (pintype "bidirectional"))
      (node (ref "U14") (pin "21") (pinfunction "AGND_21") (pintype "bidirectional"))
      (node (ref "U14") (pin "3") (pinfunction "GND_3") (pintype "bidirectional"))
      (node (ref "U14") (pin "5") (pinfunction "GND_5") (pintype "bidirectional"))
      (node (ref "U2") (pin "RING1") (pinfunction "SLEEVE_RING1") (pintype "bidirectional"))
      (node (ref "U3") (pin "RING1") (pinfunction "SLEEVE_RING1") (pintype "bidirectional"))
      (node (ref "U4") (pin "RING1") (pinfunction "SLEEVE_RING1") (pintype "bidirectional"))
      (node (ref "U5") (pin "RING1") (pinfunction "SLEEVE_RING1") (pintype "bidirectional"))
      (node (ref "U6") (pin "RING1") (pinfunction "SLEEVE_RING1") (pintype "bidirectional"))
      (node (ref "U7") (pin "RING1") (pinfunction "SLEEVE_RING1") (pintype "bidirectional"))
      (node (ref "U8") (pin "RING1") (pinfunction "SLEEVE_RING1") (pintype "bidirectional"))
      (node (ref "U9") (pin "RING1") (pinfunction "SLEEVE_RING1") (pintype "bidirectional"))
    )
    (net (code "40") (name "Net-(IC1-VI)") (class "Default")
      (node (ref "C3") (pin "+") (pinfunction "+_+") (pintype "passive"))
      (node (ref "D1") (pin "C") (pinfunction "C_C") (pintype "passive"))
      (node (ref "IC1") (pin "1") (pinfunction "VI_1") (pintype "input"))
      (node (ref "J2") (pin "PWR") (pinfunction "PWR_PWR") (pintype "bidirectional"))
    )
    (net (code "41") (name "Net-(LED1-C)") (class "Default")
      (node (ref "LED1") (pin "K") (pinfunction "C_K") (pintype "passive"))
      (node (ref "Q1") (pin "1") (pinfunction "C_1") (pintype "passive"))
      (node (ref "U2") (pin "SHIELD") (pinfunction "LEFT_SHIELD") (pintype "bidirectional"))
    )
    (net (code "42") (name "Net-(LED1-PadA)") (class "Default")
      (node (ref "LED1") (pin "A") (pinfunction "A_A") (pintype "passive"))
      (node (ref "R1") (pin "1") (pinfunction "1_1") (pintype "passive"))
    )
    (net (code "43") (name "Net-(LED2-C)") (class "Default")
      (node (ref "LED2") (pin "K") (pinfunction "C_K") (pintype "passive"))
      (node (ref "Q2") (pin "1") (pinfunction "C_1") (pintype "passive"))
      (node (ref "U3") (pin "SHIELD") (pinfunction "LEFT_SHIELD") (pintype "bidirectional"))
    )
    (net (code "44") (name "Net-(LED2-PadA)") (class "Default")
      (node (ref "LED2") (pin "A") (pinfunction "A_A") (pintype "passive"))
      (node (ref "R2") (pin "1") (pinfunction "1_1") (pintype "passive"))
    )
    (net (code "45") (name "Net-(LED3-C)") (class "Default")
      (node (ref "LED3") (pin "K") (pinfunction "C_K") (pintype "passive"))
      (node (ref "Q3") (pin "1") (pinfunction "C_1") (pintype "passive"))
      (node (ref "U4") (pin "SHIELD") (pinfunction "LEFT_SHIELD") (pintype "bidirectional"))
    )
    (net (code "46") (name "Net-(LED3-PadA)") (class "Default")
      (node (ref "LED3") (pin "A") (pinfunction "A_A") (pintype "passive"))
      (node (ref "R3") (pin "1") (pinfunction "1_1") (pintype "passive"))
    )
    (net (code "47") (name "Net-(LED4-C)") (class "Default")
      (node (ref "LED4") (pin "K") (pinfunction "C_K") (pintype "passive"))
      (node (ref "Q4") (pin "1") (pinfunction "C_1") (pintype "passive"))
      (node (ref "U5") (pin "SHIELD") (pinfunction "LEFT_SHIELD") (pintype "bidirectional"))
    )
    (net (code "48") (name "Net-(LED4-PadA)") (class "Default")
      (node (ref "LED4") (pin "A") (pinfunction "A_A") (pintype "passive"))
      (node (ref "R4") (pin "1") (pinfunction "1_1") (pintype "passive"))
    )
    (net (code "49") (name "Net-(LED5-C)") (class "Default")
      (node (ref "LED5") (pin "K") (pinfunction "C_K") (pintype "passive"))
      (node (ref "Q5") (pin "1") (pinfunction "C_1") (pintype "passive"))
      (node (ref "U6") (pin "SHIELD") (pinfunction "LEFT_SHIELD") (pintype "bidirectional"))
    )
    (net (code "50") (name "Net-(LED5-PadA)") (class "Default")
      (node (ref "LED5") (pin "A") (pinfunction "A_A") (pintype "passive"))
      (node (ref "R5") (pin "1") (pinfunction "1_1") (pintype "passive"))
    )
    (net (code "51") (name "Net-(LED6-C)") (class "Default")
      (node (ref "LED6") (pin "K") (pinfunction "C_K") (pintype "passive"))
      (node (ref "Q6") (pin "1") (pinfunction "C_1") (pintype "passive"))
      (node (ref "U7") (pin "SHIELD") (pinfunction "LEFT_SHIELD") (pintype "bidirectional"))
    )
    (net (code "52") (name "Net-(LED6-PadA)") (class "Default")
      (node (ref "LED6") (pin "A") (pinfunction "A_A") (pintype "passive"))
      (node (ref "R6") (pin "1") (pinfunction "1_1") (pintype "passive"))
    )
    (net (code "53") (name "Net-(LED7-C)") (class "Default")
      (node (ref "LED7") (pin "K") (pinfunction "C_K") (pintype "passive"))
      (node (ref "Q7") (pin "1") (pinfunction "C_1") (pintype "passive"))
      (node (ref "U8") (pin "SHIELD") (pinfunction "LEFT_SHIELD") (pintype "bidirectional"))
    )
    (net (code "54") (name "Net-(LED7-PadA)") (class "Default")
      (node (ref "LED7") (pin "A") (pinfunction "A_A") (pintype "passive"))
      (node (ref "R7") (pin "1") (pinfunction "1_1") (pintype "passive"))
    )
    (net (code "55") (name "Net-(LED8-C)") (class "Default")
      (node (ref "LED8") (pin "K") (pinfunction "C_K") (pintype "passive"))
      (node (ref "Q8") (pin "1") (pinfunction "C_1") (pintype "passive"))
      (node (ref "U9") (pin "SHIELD") (pinfunction "LEFT_SHIELD") (pintype "bidirectional"))
    )
    (net (code "56") (name "Net-(LED8-PadA)") (class "Default")
      (node (ref "LED8") (pin "A") (pinfunction "A_A") (pintype "passive"))
      (node (ref "R8") (pin "1") (pinfunction "1_1") (pintype "passive"))
    )
    (net (code "57") (name "Net-(LED9-C)") (class "Default")
      (node (ref "LED9") (pin "K") (pinfunction "C_K") (pintype "passive"))
      (node (ref "Q9") (pin "1") (pinfunction "C_1") (pintype "passive"))
      (node (ref "U10") (pin "SHIELD") (pinfunction "LEFT_SHIELD") (pintype "bidirectional"))
    )
    (net (code "58") (name "Net-(LED9-PadA)") (class "Default")
      (node (ref "LED9") (pin "A") (pinfunction "A_A") (pintype "passive"))
      (node (ref "R9") (pin "1") (pinfunction "1_1") (pintype "passive"))
    )
    (net (code "59") (name "Net-(LED10-C)") (class "Default")
      (node (ref "LED10") (pin "K") (pinfunction "C_K") (pintype "passive"))
      (node (ref "Q10") (pin "1") (pinfunction "C_1") (pintype "passive"))
      (node (ref "U11") (pin "SHIELD") (pinfunction "LEFT_SHIELD") (pintype "bidirectional"))
    )
    (net (code "60") (name "Net-(LED10-PadA)") (class "Default")
      (node (ref "LED10") (pin "A") (pinfunction "A_A") (pintype "passive"))
      (node (ref "R10") (pin "1") (pinfunction "1_1") (pintype "passive"))
    )
    (net (code "61") (name "Net-(LED11-C)") (class "Default")
      (node (ref "LED11") (pin "K") (pinfunction "C_K") (pintype "passive"))
      (node (ref "Q11") (pin "1") (pinfunction "C_1") (pintype "passive"))
      (node (ref "U12") (pin "SHIELD") (pinfunction "LEFT_SHIELD") (pintype "bidirectional"))
    )
    (net (code "62") (name "Net-(LED11-PadA)") (class "Default")
      (node (ref "LED11") (pin "A") (pinfunction "A_A") (pintype "passive"))
      (node (ref "R11") (pin "1") (pinfunction "1_1") (pintype "passive"))
    )
    (net (code "63") (name "Net-(LED12-C)") (class "Default")
      (node (ref "LED12") (pin "K") (pinfunction "C_K") (pintype "passive"))
      (node (ref "Q12") (pin "1") (pinfunction "C_1") (pintype "passive"))
      (node (ref "U13") (pin "SHIELD") (pinfunction "LEFT_SHIELD") (pintype "bidirectional"))
    )
    (net (code "64") (name "Net-(LED12-PadA)") (class "Default")
      (node (ref "LED12") (pin "A") (pinfunction "A_A") (pintype "passive"))
      (node (ref "R12") (pin "1") (pinfunction "1_1") (pintype "passive"))
    )
    (net (code "65") (name "Net-(LED13-PadA)") (class "Default")
      (node (ref "LED13") (pin "A") (pinfunction "A_A") (pintype "passive"))
      (node (ref "R14") (pin "1") (pinfunction "1_1") (pintype "passive"))
    )
    (net (code "66") (name "Net-(LED14-C)") (class "Default")
      (node (ref "JP6") (pin "3") (pinfunction "3_3") (pintype "passive"))
      (node (ref "LED14") (pin "K") (pinfunction "C_K") (pintype "passive"))
      (node (ref "Q13") (pin "1") (pinfunction "C_1") (pintype "passive"))
    )
    (net (code "67") (name "Net-(LED14-PadA)") (class "Default")
      (node (ref "LED14") (pin "A") (pinfunction "A_A") (pintype "passive"))
      (node (ref "R38") (pin "2") (pinfunction "2_2") (pintype "passive"))
    )
    (net (code "68") (name "Net-(LED15-C)") (class "Default")
      (node (ref "JP7") (pin "3") (pinfunction "3_3") (pintype "passive"))
      (node (ref "LED15") (pin "K") (pinfunction "C_K") (pintype "passive"))
      (node (ref "Q14") (pin "1") (pinfunction "C_1") (pintype "passive"))
    )
    (net (code "69") (name "Net-(LED15-PadA)") (class "Default")
      (node (ref "LED15") (pin "A") (pinfunction "A_A") (pintype "passive"))
      (node (ref "R39") (pin "2") (pinfunction "2_2") (pintype "passive"))
    )
    (net (code "70") (name "Net-(LED16-C)") (class "Default")
      (node (ref "JP8") (pin "3") (pinfunction "3_3") (pintype "passive"))
      (node (ref "LED16") (pin "K") (pinfunction "C_K") (pintype "passive"))
      (node (ref "Q15") (pin "1") (pinfunction "C_1") (pintype "passive"))
    )
    (net (code "71") (name "Net-(LED16-PadA)") (class "Default")
      (node (ref "LED16") (pin "A") (pinfunction "A_A") (pintype "passive"))
      (node (ref "R40") (pin "2") (pinfunction "2_2") (pintype "passive"))
    )
    (net (code "72") (name "Net-(LED17-C)") (class "Default")
      (node (ref "JP9") (pin "3") (pinfunction "3_3") (pintype "passive"))
      (node (ref "LED17") (pin "K") (pinfunction "C_K") (pintype "passive"))
      (node (ref "Q16") (pin "1") (pinfunction "C_1") (pintype "passive"))
    )
    (net (code "73") (name "Net-(LED17-PadA)") (class "Default")
      (node (ref "LED17") (pin "A") (pinfunction "A_A") (pintype "passive"))
      (node (ref "R41") (pin "2") (pinfunction "2_2") (pintype "passive"))
    )
    (net (code "74") (name "Net-(Q13-B)") (class "Default")
      (node (ref "Q13") (pin "2") (pinfunction "B_2") (pintype "passive"))
      (node (ref "R30") (pin "1") (pinfunction "1_1") (pintype "passive"))
      (node (ref "R31") (pin "1") (pinfunction "1_1") (pintype "passive"))
    )
    (net (code "75") (name "Net-(Q14-B)") (class "Default")
      (node (ref "Q14") (pin "2") (pinfunction "B_2") (pintype "passive"))
      (node (ref "R32") (pin "1") (pinfunction "1_1") (pintype "passive"))
      (node (ref "R33") (pin "1") (pinfunction "1_1") (pintype "passive"))
    )
    (net (code "76") (name "Net-(Q15-B)") (class "Default")
      (node (ref "Q15") (pin "2") (pinfunction "B_2") (pintype "passive"))
      (node (ref "R34") (pin "1") (pinfunction "1_1") (pintype "passive"))
      (node (ref "R35") (pin "1") (pinfunction "1_1") (pintype "passive"))
    )
    (net (code "77") (name "Net-(Q16-B)") (class "Default")
      (node (ref "Q16") (pin "2") (pinfunction "B_2") (pintype "passive"))
      (node (ref "R36") (pin "1") (pinfunction "1_1") (pintype "passive"))
      (node (ref "R37") (pin "1") (pinfunction "1_1") (pintype "passive"))
    )
    (net (code "78") (name "Net-(R15-Pad2)") (class "Default")
      (node (ref "R15") (pin "2") (pinfunction "2_2") (pintype "passive"))
      (node (ref "S1") (pin "1") (pinfunction "1_1") (pintype "passive"))
    )
    (net (code "79") (name "Net-(R16-Pad2)") (class "Default")
      (node (ref "R16") (pin "2") (pinfunction "2_2") (pintype "passive"))
      (node (ref "S2") (pin "1") (pinfunction "1_1") (pintype "passive"))
    )
    (net (code "80") (name "Net-(R17-Pad2)") (class "Default")
      (node (ref "R17") (pin "2") (pinfunction "2_2") (pintype "passive"))
      (node (ref "S3") (pin "1") (pinfunction "1_1") (pintype "passive"))
    )
    (net (code "81") (name "Net-(R18-Pad2)") (class "Default")
      (node (ref "R18") (pin "2") (pinfunction "2_2") (pintype "passive"))
      (node (ref "S4") (pin "1") (pinfunction "1_1") (pintype "passive"))
    )
    (net (code "82") (name "Net-(R19-Pad2)") (class "Default")
      (node (ref "R19") (pin "2") (pinfunction "2_2") (pintype "passive"))
      (node (ref "S5") (pin "1") (pinfunction "1_1") (pintype "passive"))
    )
    (net (code "83") (name "Net-(R20-Pad2)") (class "Default")
      (node (ref "R20") (pin "2") (pinfunction "2_2") (pintype "passive"))
      (node (ref "S6") (pin "1") (pinfunction "1_1") (pintype "passive"))
    )
    (net (code "84") (name "Net-(R21-Pad2)") (class "Default")
      (node (ref "R21") (pin "2") (pinfunction "2_2") (pintype "passive"))
      (node (ref "S7") (pin "1") (pinfunction "1_1") (pintype "passive"))
    )
    (net (code "85") (name "Net-(R22-Pad2)") (class "Default")
      (node (ref "R22") (pin "2") (pinfunction "2_2") (pintype "passive"))
      (node (ref "S8") (pin "1") (pinfunction "1_1") (pintype "passive"))
    )
    (net (code "86") (name "Net-(R23-Pad2)") (class "Default")
      (node (ref "R23") (pin "2") (pinfunction "2_2") (pintype "passive"))
      (node (ref "S9") (pin "1") (pinfunction "1_1") (pintype "passive"))
    )
    (net (code "87") (name "Net-(R24-Pad2)") (class "Default")
      (node (ref "R24") (pin "2") (pinfunction "2_2") (pintype "passive"))
      (node (ref "S10") (pin "1") (pinfunction "1_1") (pintype "passive"))
    )
    (net (code "88") (name "Net-(R25-Pad2)") (class "Default")
      (node (ref "R25") (pin "2") (pinfunction "2_2") (pintype "passive"))
      (node (ref "S11") (pin "1") (pinfunction "1_1") (pintype "passive"))
    )
    (net (code "89") (name "Net-(R26-Pad2)") (class "Default")
      (node (ref "R26") (pin "2") (pinfunction "2_2") (pintype "passive"))
      (node (ref "S12") (pin "1") (pinfunction "1_1") (pintype "passive"))
    )
    (net (code "90") (name "Net-(U$1-RG1)") (class "Default")
      (node (ref "R29") (pin "2") (pinfunction "2_2") (pintype "passive"))
      (node (ref "U$1") (pin "8") (pinfunction "RG1_8") (pintype "bidirectional"))
    )
    (net (code "91") (name "Net-(U$1-RG2)") (class "Default")
      (node (ref "R29") (pin "1") (pinfunction "1_1") (pintype "passive"))
      (node (ref "U$1") (pin "9") (pinfunction "RG2_9") (pintype "bidirectional"))
    )
    (net (code "92") (name "Net-(U$1-VIN+)") (class "Default")
      (node (ref "JP5") (pin "2") (pinfunction "2_2") (pintype "passive"))
      (node (ref "U$1") (pin "6") (pinfunction "VIN+_6") (pintype "bidirectional"))
    )
    (net (code "93") (name "Net-(U$1-VIN-)") (class "Default")
      (node (ref "JP5") (pin "1") (pinfunction "1_1") (pintype "passive"))
      (node (ref "U$1") (pin "7") (pinfunction "VIN-_7") (pintype "bidirectional"))
    )
    (net (code "94") (name "Net-(U$1-VREF5)") (class "Default")
      (node (ref "U$1") (pin "15") (pinfunction "VREF5_15") (pintype "bidirectional"))
      (node (ref "U$1") (pin "4") (pinfunction "VREFOUT_4") (pintype "bidirectional"))
    )
    (net (code "95") (name "Net-(U14-PB6(XTAL1{slash}TOSC1))") (class "Default")
      (node (ref "C1") (pin "2") (pinfunction "2_2") (pintype "passive"))
      (node (ref "U14") (pin "7") (pinfunction "PB6(XTAL1/TOSC1)_7") (pintype "bidirectional"))
      (node (ref "Y1") (pin "2") (pinfunction "2_2") (pintype "passive"))
    )
    (net (code "96") (name "Net-(U14-PB7(XTAL2{slash}TOSC2))") (class "Default")
      (node (ref "C2") (pin "2") (pinfunction "2_2") (pintype "passive"))
      (node (ref "U14") (pin "8") (pinfunction "PB7(XTAL2/TOSC2)_8") (pintype "bidirectional"))
      (node (ref "Y1") (pin "1") (pinfunction "1_1") (pintype "passive"))
    )
    (net (code "97") (name "unconnected-(IC2-GPB4-Pad5)") (class "Default")
      (node (ref "IC2") (pin "5") (pinfunction "GPB4_5") (pintype "bidirectional"))
    )
    (net (code "98") (name "unconnected-(IC2-GPB5-Pad6)") (class "Default")
      (node (ref "IC2") (pin "6") (pinfunction "GPB5_6") (pintype "bidirectional"))
    )
    (net (code "99") (name "unconnected-(IC2-GPB6-Pad7)") (class "Default")
      (node (ref "IC2") (pin "7") (pinfunction "GPB6_7") (pintype "bidirectional"))
    )
    (net (code "100") (name "unconnected-(IC2-GPB7-Pad8)") (class "Default")
      (node (ref "IC2") (pin "8") (pinfunction "GPB7_8") (pintype "bidirectional"))
    )
    (net (code "101") (name "unconnected-(IC2-INTA-Pad20)") (class "Default")
      (node (ref "IC2") (pin "20") (pinfunction "INTA_20") (pintype "output"))
    )
    (net (code "102") (name "unconnected-(IC2-INTB-Pad19)") (class "Default")
      (node (ref "IC2") (pin "19") (pinfunction "INTB_19") (pintype "output"))
    )
    (net (code "103") (name "unconnected-(J2-PadGNDBREAK)") (class "Default")
      (node (ref "J2") (pin "GNDBREAK") (pinfunction "GNDBREAK_GNDBREAK") (pintype "bidirectional"))
    )
    (net (code "104") (name "unconnected-(U$1-VREF2.5-Pad14)") (class "Default")
      (node (ref "U$1") (pin "14") (pinfunction "VREF2.5_14") (pintype "bidirectional"))
    )
    (net (code "105") (name "unconnected-(U$1-VREF10-Pad16)") (class "Default")
      (node (ref "U$1") (pin "16") (pinfunction "VREF10_16") (pintype "bidirectional"))
    )
    (net (code "106") (name "unconnected-(U$1-VREFBG-Pad13)") (class "Default")
      (node (ref "U$1") (pin "13") (pinfunction "VREFBG_13") (pintype "bidirectional"))
    )
    (net (code "107") (name "unconnected-(U2-RIGHT-PadTIP)") (class "Default")
      (node (ref "U2") (pin "TIP") (pinfunction "RIGHT_TIP") (pintype "bidirectional"))
    )
    (net (code "108") (name "unconnected-(U3-RIGHT-PadTIP)") (class "Default")
      (node (ref "U3") (pin "TIP") (pinfunction "RIGHT_TIP") (pintype "bidirectional"))
    )
    (net (code "109") (name "unconnected-(U4-RIGHT-PadTIP)") (class "Default")
      (node (ref "U4") (pin "TIP") (pinfunction "RIGHT_TIP") (pintype "bidirectional"))
    )
    (net (code "110") (name "unconnected-(U5-RIGHT-PadTIP)") (class "Default")
      (node (ref "U5") (pin "TIP") (pinfunction "RIGHT_TIP") (pintype "bidirectional"))
    )
    (net (code "111") (name "unconnected-(U6-RIGHT-PadTIP)") (class "Default")
      (node (ref "U6") (pin "TIP") (pinfunction "RIGHT_TIP") (pintype "bidirectional"))
    )
    (net (code "112") (name "unconnected-(U7-RIGHT-PadTIP)") (class "Default")
      (node (ref "U7") (pin "TIP") (pinfunction "RIGHT_TIP") (pintype "bidirectional"))
    )
    (net (code "113") (name "unconnected-(U8-RIGHT-PadTIP)") (class "Default")
      (node (ref "U8") (pin "TIP") (pinfunction "RIGHT_TIP") (pintype "bidirectional"))
    )
    (net (code "114") (name "unconnected-(U9-RIGHT-PadTIP)") (class "Default")
      (node (ref "U9") (pin "TIP") (pinfunction "RIGHT_TIP") (pintype "bidirectional"))
    )
    (net (code "115") (name "unconnected-(U10-RIGHT-PadTIP)") (class "Default")
      (node (ref "U10") (pin "TIP") (pinfunction "RIGHT_TIP") (pintype "bidirectional"))
    )
    (net (code "116") (name "unconnected-(U11-RIGHT-PadTIP)") (class "Default")
      (node (ref "U11") (pin "TIP") (pinfunction "RIGHT_TIP") (pintype "bidirectional"))
    )
    (net (code "117") (name "unconnected-(U12-RIGHT-PadTIP)") (class "Default")
      (node (ref "U12") (pin "TIP") (pinfunction "RIGHT_TIP") (pintype "bidirectional"))
    )
    (net (code "118") (name "unconnected-(U13-RIGHT-PadTIP)") (class "Default")
      (node (ref "U13") (pin "TIP") (pinfunction "RIGHT_TIP") (pintype "bidirectional"))
    )
  )
)
